# AQPCB.net
KiCad netlist of a schematic drawn in EAGLE
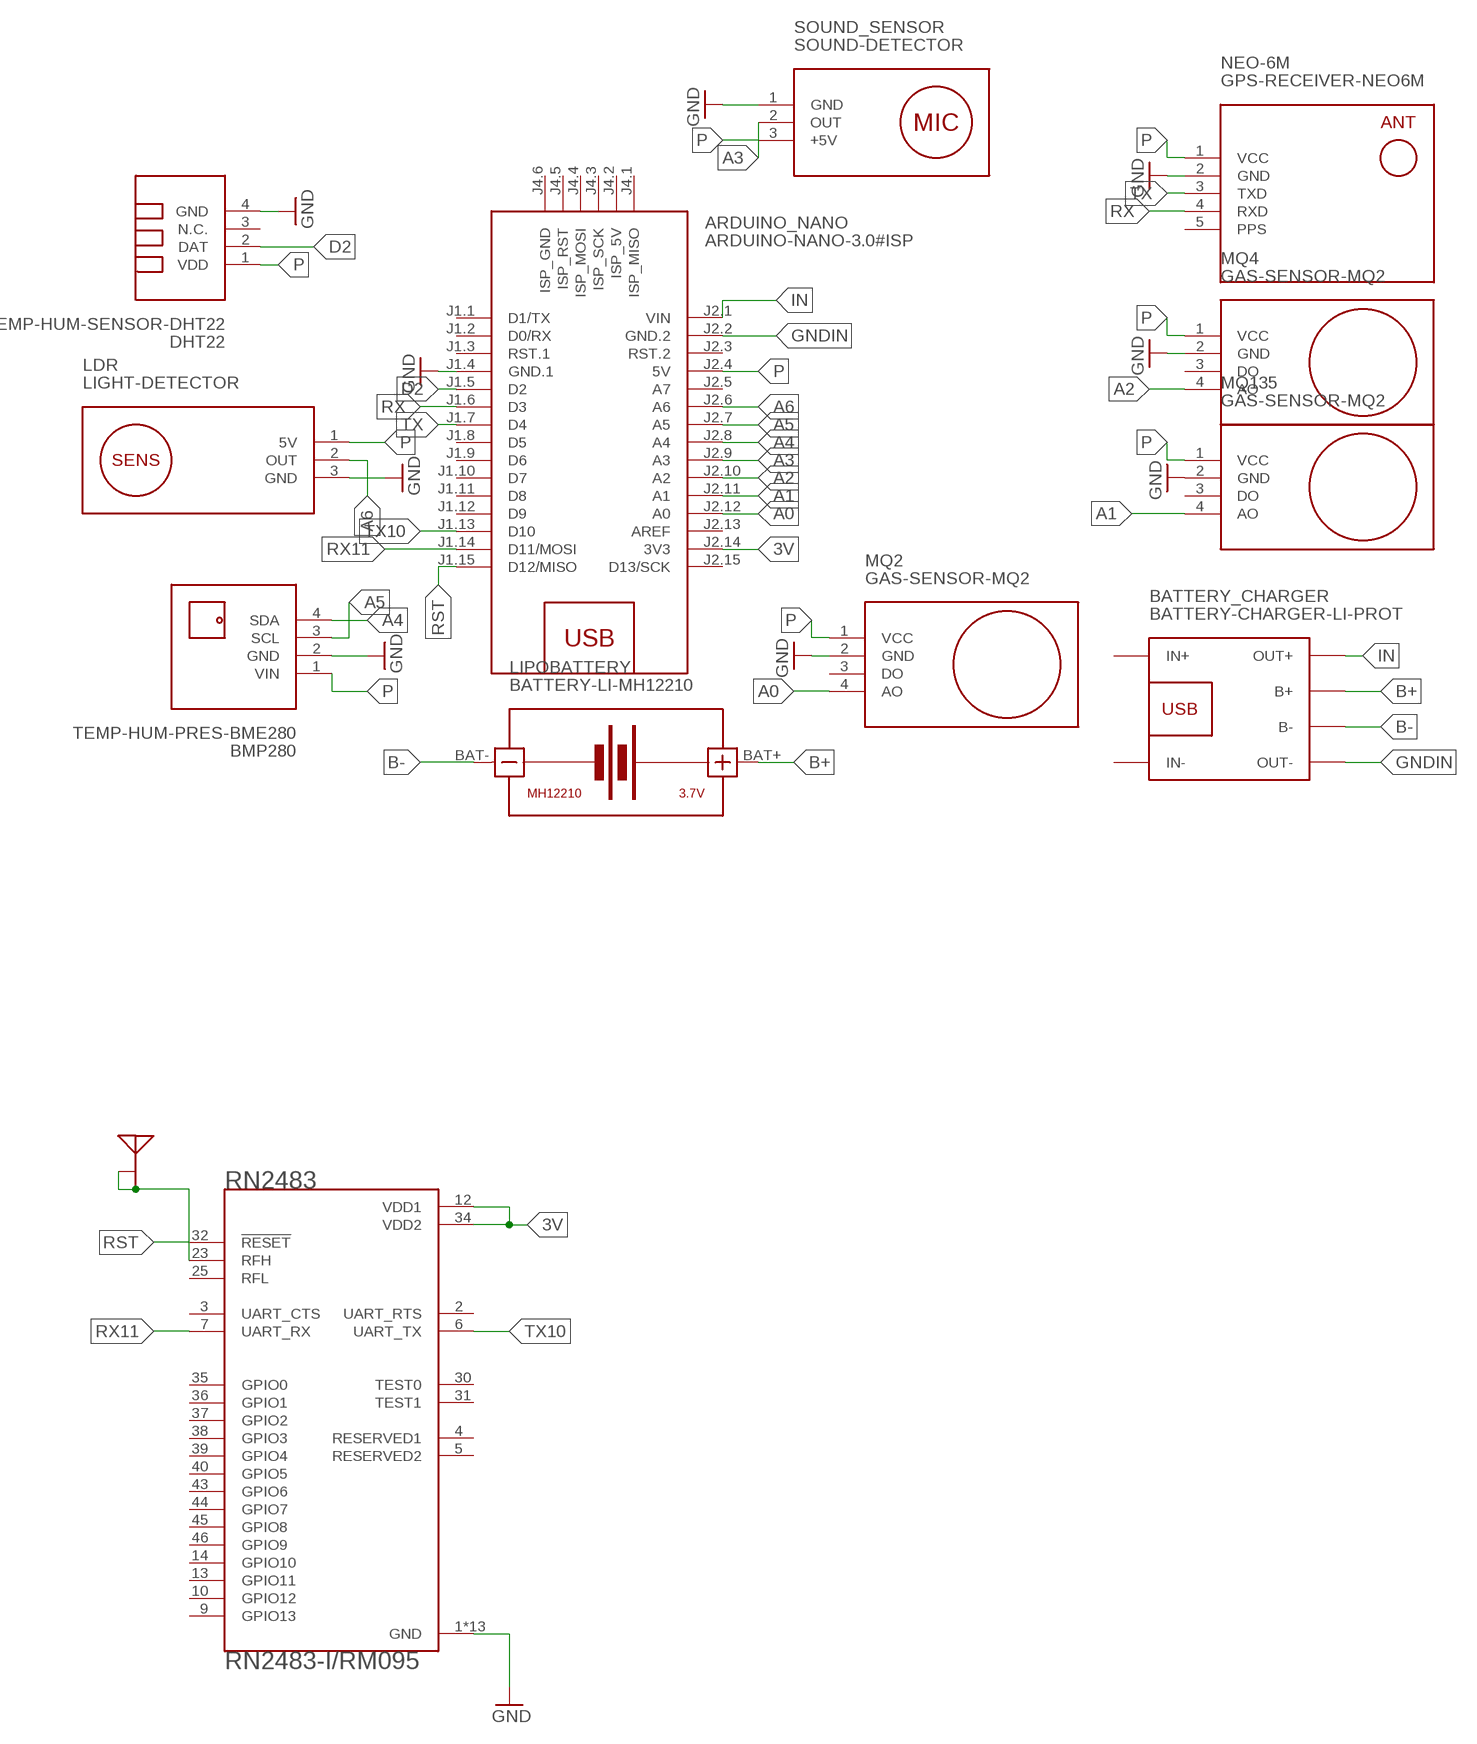
[diagram p0: schematic, sheet 1]

(export (version "E")
  (design (tool "Eeschema 10.0.6"))
  (components
    (comp (ref "ANTENNA")
      (value "CHIP")
      (footprint "eagle-import:2450AT18B100")
      (libsource (lib "eagle-import") (part "CHIP"))
    )
    (comp (ref "ARDUINO_NANO")
      (value "ARDUINO-NANO-3.0#ISP")
      (footprint "eagle-import:ARDUINO-NANO-3.0#ISP")
      (libsource (lib "eagle-import") (part "ARDUINO-NANO-3.0#ISP"))
    )
    (comp (ref "BATTERY_CHARGER")
      (value "BATTERY-CHARGER-LI-PROT")
      (footprint "eagle-import:BATTERY-CHARGER-LI-PROT")
      (libsource (lib "eagle-import") (part "BATTERY-CHARGER-LI-PROT"))
    )
    (comp (ref "BMP280")
      (value "TEMP-HUM-PRES-BME280")
      (footprint "eagle-import:TEMP-HUM-PRES-BME280")
      (libsource (lib "eagle-import") (part "TEMP-HUM-PRES-BME280"))
    )
    (comp (ref "DHT22")
      (value "TEMP-HUM-SENSOR-DHT22")
      (footprint "eagle-import:TEMP-HUM-SENSOR-DHT22")
      (libsource (lib "eagle-import") (part "TEMP-HUM-SENSOR-DHT22"))
    )
    (comp (ref "LDR")
      (value "LIGHT-DETECTOR")
      (footprint "eagle-import:LIGHT-DETECTOR")
      (libsource (lib "eagle-import") (part "LIGHT-DETECTOR"))
    )
    (comp (ref "LIPOBATTERY")
      (value "BATTERY-LI-MH12210")
      (footprint "eagle-import:BATTERY-LI-MH12210")
      (libsource (lib "eagle-import") (part "BATTERY-LI-MH12210"))
    )
    (comp (ref "MQ2")
      (value "GAS-SENSOR-MQ2")
      (footprint "eagle-import:GAS-SENSOR-MQ2")
      (libsource (lib "eagle-import") (part "GAS-SENSOR-MQ2"))
    )
    (comp (ref "MQ4")
      (value "GAS-SENSOR-MQ2")
      (footprint "eagle-import:GAS-SENSOR-MQ2")
      (libsource (lib "eagle-import") (part "GAS-SENSOR-MQ2"))
    )
    (comp (ref "MQ135")
      (value "GAS-SENSOR-MQ2")
      (footprint "eagle-import:GAS-SENSOR-MQ2")
      (libsource (lib "eagle-import") (part "GAS-SENSOR-MQ2"))
    )
    (comp (ref "NEO-6M")
      (value "GPS-RECEIVER-NEO6M")
      (footprint "eagle-import:GPS-RECEIVER-NEO6M")
      (libsource (lib "eagle-import") (part "GPS-RECEIVER-NEO6M"))
    )
    (comp (ref "RN2483")
      (value "RN2483-I/RM095")
      (footprint "eagle-import:MICROCHIP_RN2483-I_RM095")
      (fields (field (name "MF") "Microchip"))
      (libsource (lib "eagle-import") (part "RN2483-I/RM095"))
    )
    (comp (ref "SOUND_SENSOR")
      (value "SOUND-DETECTOR")
      (footprint "eagle-import:SOUND-DETECTOR")
      (libsource (lib "eagle-import") (part "SOUND-DETECTOR"))
    )
  )
  (nets
    (net (code "1") (name "/PPS") (class "Default")
      (node (ref "NEO-6M") (pin "5") (pinfunction "PPS_5") (pintype "power_in"))
    )
    (net (code "2") (name "3V") (class "Default")
      (node (ref "ARDUINO_NANO") (pin "J2.14") (pinfunction "3V3_J2.14") (pintype "power_in"))
      (node (ref "RN2483") (pin "12") (pinfunction "VDD1_12") (pintype "power_in"))
      (node (ref "RN2483") (pin "34") (pinfunction "VDD2_34") (pintype "power_in"))
    )
    (net (code "3") (name "A0") (class "Default")
      (node (ref "ARDUINO_NANO") (pin "J2.12") (pinfunction "A0_J2.12") (pintype "bidirectional"))
      (node (ref "MQ2") (pin "4") (pinfunction "AO_4") (pintype "output"))
    )
    (net (code "4") (name "A1") (class "Default")
      (node (ref "ARDUINO_NANO") (pin "J2.11") (pinfunction "A1_J2.11") (pintype "bidirectional"))
      (node (ref "MQ135") (pin "4") (pinfunction "AO_4") (pintype "output"))
    )
    (net (code "5") (name "A2") (class "Default")
      (node (ref "ARDUINO_NANO") (pin "J2.10") (pinfunction "A2_J2.10") (pintype "bidirectional"))
      (node (ref "MQ4") (pin "4") (pinfunction "AO_4") (pintype "output"))
    )
    (net (code "6") (name "A3") (class "Default")
      (node (ref "ARDUINO_NANO") (pin "J2.9") (pinfunction "A3_J2.9") (pintype "bidirectional"))
      (node (ref "SOUND_SENSOR") (pin "2") (pinfunction "OUT_2") (pintype "output"))
    )
    (net (code "7") (name "A4") (class "Default")
      (node (ref "ARDUINO_NANO") (pin "J2.8") (pinfunction "A4_J2.8") (pintype "bidirectional"))
      (node (ref "BMP280") (pin "4") (pinfunction "SDA_4") (pintype "bidirectional"))
    )
    (net (code "8") (name "A5") (class "Default")
      (node (ref "ARDUINO_NANO") (pin "J2.7") (pinfunction "A5_J2.7") (pintype "bidirectional"))
      (node (ref "BMP280") (pin "3") (pinfunction "SCL_3") (pintype "bidirectional"))
    )
    (net (code "9") (name "A6") (class "Default")
      (node (ref "ARDUINO_NANO") (pin "J2.6") (pinfunction "A6_J2.6") (pintype "bidirectional"))
      (node (ref "LDR") (pin "2") (pinfunction "OUT_2") (pintype "bidirectional"))
    )
    (net (code "10") (name "B+") (class "Default")
      (node (ref "BATTERY_CHARGER") (pin "B+") (pinfunction "B+_B+") (pintype "bidirectional"))
      (node (ref "LIPOBATTERY") (pin "BAT+") (pinfunction "BAT+_BAT+") (pintype "power_in"))
    )
    (net (code "11") (name "B-") (class "Default")
      (node (ref "BATTERY_CHARGER") (pin "B-") (pinfunction "B-_B-") (pintype "bidirectional"))
      (node (ref "LIPOBATTERY") (pin "BAT-") (pinfunction "BAT-_BAT-") (pintype "power_in"))
    )
    (net (code "12") (name "D2") (class "Default")
      (node (ref "ARDUINO_NANO") (pin "J1.5") (pinfunction "D2_J1.5") (pintype "bidirectional"))
      (node (ref "DHT22") (pin "2") (pinfunction "DAT_2") (pintype "bidirectional"))
    )
    (net (code "13") (name "GND") (class "Default")
      (node (ref "ARDUINO_NANO") (pin "J1.4") (pinfunction "GND.1_J1.4") (pintype "power_in"))
      (node (ref "BMP280") (pin "2") (pinfunction "GND_2") (pintype "power_in"))
      (node (ref "DHT22") (pin "4") (pinfunction "GND_4") (pintype "power_in"))
      (node (ref "LDR") (pin "3") (pinfunction "GND_3") (pintype "power_in"))
      (node (ref "MQ135") (pin "2") (pinfunction "GND_2") (pintype "power_in"))
      (node (ref "MQ2") (pin "2") (pinfunction "GND_2") (pintype "power_in"))
      (node (ref "MQ4") (pin "2") (pinfunction "GND_2") (pintype "power_in"))
      (node (ref "NEO-6M") (pin "2") (pinfunction "GND_2") (pintype "bidirectional"))
      (node (ref "RN2483") (pin "1") (pinfunction "GND_1") (pintype "passive"))
      (node (ref "RN2483") (pin "11") (pinfunction "GND_11") (pintype "passive"))
      (node (ref "RN2483") (pin "20") (pinfunction "GND_20") (pintype "passive"))
      (node (ref "RN2483") (pin "21") (pinfunction "GND_21") (pintype "passive"))
      (node (ref "RN2483") (pin "22") (pinfunction "GND_22") (pintype "passive"))
      (node (ref "RN2483") (pin "24") (pinfunction "GND_24") (pintype "passive"))
      (node (ref "RN2483") (pin "26") (pinfunction "GND_26") (pintype "passive"))
      (node (ref "RN2483") (pin "27") (pinfunction "GND_27") (pintype "passive"))
      (node (ref "RN2483") (pin "28") (pinfunction "GND_28") (pintype "passive"))
      (node (ref "RN2483") (pin "33") (pinfunction "GND_33") (pintype "passive"))
      (node (ref "RN2483") (pin "41") (pinfunction "GND_41") (pintype "passive"))
      (node (ref "RN2483") (pin "47") (pinfunction "GND_47") (pintype "passive"))
      (node (ref "RN2483") (pin "8") (pinfunction "GND_8") (pintype "passive"))
      (node (ref "SOUND_SENSOR") (pin "1") (pinfunction "GND_1") (pintype "power_in"))
    )
    (net (code "14") (name "GNDIN") (class "Default")
      (node (ref "ARDUINO_NANO") (pin "J2.2") (pinfunction "GND.2_J2.2") (pintype "power_in"))
      (node (ref "BATTERY_CHARGER") (pin "OUT-") (pinfunction "OUT-_OUT-") (pintype "bidirectional"))
    )
    (net (code "15") (name "IN") (class "Default")
      (node (ref "ARDUINO_NANO") (pin "J2.1") (pinfunction "VIN_J2.1") (pintype "power_in"))
      (node (ref "BATTERY_CHARGER") (pin "OUT+") (pinfunction "OUT+_OUT+") (pintype "bidirectional"))
    )
    (net (code "16") (name "Net-(RN2483-RFH)") (class "Default")
      (node (ref "ANTENNA") (pin "FEED") (pinfunction "FEED_FEED") (pintype "bidirectional"))
      (node (ref "ANTENNA") (pin "GND") (pinfunction "GND_GND") (pintype "bidirectional"))
      (node (ref "RN2483") (pin "23") (pinfunction "RFH_23") (pintype "input"))
    )
    (net (code "17") (name "P") (class "Default")
      (node (ref "ARDUINO_NANO") (pin "J2.4") (pinfunction "5V_J2.4") (pintype "power_in"))
      (node (ref "BMP280") (pin "1") (pinfunction "VIN_1") (pintype "power_in"))
      (node (ref "DHT22") (pin "1") (pinfunction "VDD_1") (pintype "power_in"))
      (node (ref "LDR") (pin "1") (pinfunction "5V_1") (pintype "power_in"))
      (node (ref "MQ135") (pin "1") (pinfunction "VCC_1") (pintype "power_in"))
      (node (ref "MQ2") (pin "1") (pinfunction "VCC_1") (pintype "power_in"))
      (node (ref "MQ4") (pin "1") (pinfunction "VCC_1") (pintype "power_in"))
      (node (ref "NEO-6M") (pin "1") (pinfunction "VCC_1") (pintype "bidirectional"))
      (node (ref "SOUND_SENSOR") (pin "3") (pinfunction "+5V_3") (pintype "power_in"))
    )
    (net (code "18") (name "RST") (class "Default")
      (node (ref "ARDUINO_NANO") (pin "J1.15") (pinfunction "D12/MISO_J1.15") (pintype "bidirectional"))
      (node (ref "RN2483") (pin "32") (pinfunction "~{RESET}_32") (pintype "input"))
    )
    (net (code "19") (name "RX") (class "Default")
      (node (ref "ARDUINO_NANO") (pin "J1.6") (pinfunction "D3_J1.6") (pintype "bidirectional"))
      (node (ref "NEO-6M") (pin "4") (pinfunction "RXD_4") (pintype "power_in"))
    )
    (net (code "20") (name "RX11") (class "Default")
      (node (ref "ARDUINO_NANO") (pin "J1.14") (pinfunction "D11/MOSI_J1.14") (pintype "bidirectional"))
      (node (ref "RN2483") (pin "7") (pinfunction "UART_RX_7") (pintype "input"))
    )
    (net (code "21") (name "TX") (class "Default")
      (node (ref "ARDUINO_NANO") (pin "J1.7") (pinfunction "D4_J1.7") (pintype "bidirectional"))
      (node (ref "NEO-6M") (pin "3") (pinfunction "TXD_3") (pintype "bidirectional"))
    )
    (net (code "22") (name "TX10") (class "Default")
      (node (ref "ARDUINO_NANO") (pin "J1.13") (pinfunction "D10_J1.13") (pintype "bidirectional"))
      (node (ref "RN2483") (pin "6") (pinfunction "UART_TX_6") (pintype "output"))
    )
    (net (code "23") (name "unconnected-(ARDUINO_NANO-A7-PadJ2.5)") (class "Default")
      (node (ref "ARDUINO_NANO") (pin "J2.5") (pinfunction "A7_J2.5") (pintype "bidirectional"))
    )
    (net (code "24") (name "unconnected-(ARDUINO_NANO-AREF-PadJ2.13)") (class "Default")
      (node (ref "ARDUINO_NANO") (pin "J2.13") (pinfunction "AREF_J2.13") (pintype "bidirectional"))
    )
    (net (code "25") (name "unconnected-(ARDUINO_NANO-D0{slash}RX-PadJ1.2)") (class "Default")
      (node (ref "ARDUINO_NANO") (pin "J1.2") (pinfunction "D0/RX_J1.2") (pintype "bidirectional"))
    )
    (net (code "26") (name "unconnected-(ARDUINO_NANO-D1{slash}TX-PadJ1.1)") (class "Default")
      (node (ref "ARDUINO_NANO") (pin "J1.1") (pinfunction "D1/TX_J1.1") (pintype "bidirectional"))
    )
    (net (code "27") (name "unconnected-(ARDUINO_NANO-D5-PadJ1.8)") (class "Default")
      (node (ref "ARDUINO_NANO") (pin "J1.8") (pinfunction "D5_J1.8") (pintype "bidirectional"))
    )
    (net (code "28") (name "unconnected-(ARDUINO_NANO-D6-PadJ1.9)") (class "Default")
      (node (ref "ARDUINO_NANO") (pin "J1.9") (pinfunction "D6_J1.9") (pintype "bidirectional"))
    )
    (net (code "29") (name "unconnected-(ARDUINO_NANO-D7-PadJ1.10)") (class "Default")
      (node (ref "ARDUINO_NANO") (pin "J1.10") (pinfunction "D7_J1.10") (pintype "bidirectional"))
    )
    (net (code "30") (name "unconnected-(ARDUINO_NANO-D8-PadJ1.11)") (class "Default")
      (node (ref "ARDUINO_NANO") (pin "J1.11") (pinfunction "D8_J1.11") (pintype "bidirectional"))
    )
    (net (code "31") (name "unconnected-(ARDUINO_NANO-D9-PadJ1.12)") (class "Default")
      (node (ref "ARDUINO_NANO") (pin "J1.12") (pinfunction "D9_J1.12") (pintype "bidirectional"))
    )
    (net (code "32") (name "unconnected-(ARDUINO_NANO-D13{slash}SCK-PadJ2.15)") (class "Default")
      (node (ref "ARDUINO_NANO") (pin "J2.15") (pinfunction "D13/SCK_J2.15") (pintype "bidirectional"))
    )
    (net (code "33") (name "unconnected-(ARDUINO_NANO-ISP_5V-PadJ4.2)") (class "Default")
      (node (ref "ARDUINO_NANO") (pin "J4.2") (pinfunction "ISP_5V_J4.2") (pintype "bidirectional"))
    )
    (net (code "34") (name "unconnected-(ARDUINO_NANO-ISP_GND-PadJ4.6)") (class "Default")
      (node (ref "ARDUINO_NANO") (pin "J4.6") (pinfunction "ISP_GND_J4.6") (pintype "bidirectional"))
    )
    (net (code "35") (name "unconnected-(ARDUINO_NANO-ISP_MISO-PadJ4.1)") (class "Default")
      (node (ref "ARDUINO_NANO") (pin "J4.1") (pinfunction "ISP_MISO_J4.1") (pintype "bidirectional"))
    )
    (net (code "36") (name "unconnected-(ARDUINO_NANO-ISP_MOSI-PadJ4.4)") (class "Default")
      (node (ref "ARDUINO_NANO") (pin "J4.4") (pinfunction "ISP_MOSI_J4.4") (pintype "bidirectional"))
    )
    (net (code "37") (name "unconnected-(ARDUINO_NANO-ISP_RST-PadJ4.5)") (class "Default")
      (node (ref "ARDUINO_NANO") (pin "J4.5") (pinfunction "ISP_RST_J4.5") (pintype "bidirectional"))
    )
    (net (code "38") (name "unconnected-(ARDUINO_NANO-ISP_SCK-PadJ4.3)") (class "Default")
      (node (ref "ARDUINO_NANO") (pin "J4.3") (pinfunction "ISP_SCK_J4.3") (pintype "bidirectional"))
    )
    (net (code "39") (name "unconnected-(ARDUINO_NANO-RST.1-PadJ1.3)") (class "Default")
      (node (ref "ARDUINO_NANO") (pin "J1.3") (pinfunction "RST.1_J1.3") (pintype "bidirectional"))
    )
    (net (code "40") (name "unconnected-(ARDUINO_NANO-RST.2-PadJ2.3)") (class "Default")
      (node (ref "ARDUINO_NANO") (pin "J2.3") (pinfunction "RST.2_J2.3") (pintype "bidirectional"))
    )
    (net (code "41") (name "unconnected-(BATTERY_CHARGER-PadIN+)") (class "Default")
      (node (ref "BATTERY_CHARGER") (pin "IN+") (pinfunction "IN+_IN+") (pintype "bidirectional"))
    )
    (net (code "42") (name "unconnected-(BATTERY_CHARGER-PadIN-)") (class "Default")
      (node (ref "BATTERY_CHARGER") (pin "IN-") (pinfunction "IN-_IN-") (pintype "bidirectional"))
    )
    (net (code "43") (name "unconnected-(DHT22-N.C.-Pad3)") (class "Default")
      (node (ref "DHT22") (pin "3") (pinfunction "N.C._3") (pintype "passive"))
    )
    (net (code "44") (name "unconnected-(MQ2-DO-Pad3)") (class "Default")
      (node (ref "MQ2") (pin "3") (pinfunction "DO_3") (pintype "output"))
    )
    (net (code "45") (name "unconnected-(MQ4-DO-Pad3)") (class "Default")
      (node (ref "MQ4") (pin "3") (pinfunction "DO_3") (pintype "output"))
    )
    (net (code "46") (name "unconnected-(MQ135-DO-Pad3)") (class "Default")
      (node (ref "MQ135") (pin "3") (pinfunction "DO_3") (pintype "output"))
    )
    (net (code "47") (name "unconnected-(RN2483-GPIO0-Pad35)") (class "Default")
      (node (ref "RN2483") (pin "35") (pinfunction "GPIO0_35") (pintype "bidirectional"))
    )
    (net (code "48") (name "unconnected-(RN2483-GPIO1-Pad36)") (class "Default")
      (node (ref "RN2483") (pin "36") (pinfunction "GPIO1_36") (pintype "bidirectional"))
    )
    (net (code "49") (name "unconnected-(RN2483-GPIO2-Pad37)") (class "Default")
      (node (ref "RN2483") (pin "37") (pinfunction "GPIO2_37") (pintype "bidirectional"))
    )
    (net (code "50") (name "unconnected-(RN2483-GPIO3-Pad38)") (class "Default")
      (node (ref "RN2483") (pin "38") (pinfunction "GPIO3_38") (pintype "bidirectional"))
    )
    (net (code "51") (name "unconnected-(RN2483-GPIO4-Pad39)") (class "Default")
      (node (ref "RN2483") (pin "39") (pinfunction "GPIO4_39") (pintype "bidirectional"))
    )
    (net (code "52") (name "unconnected-(RN2483-GPIO5-Pad40)") (class "Default")
      (node (ref "RN2483") (pin "40") (pinfunction "GPIO5_40") (pintype "bidirectional"))
    )
    (net (code "53") (name "unconnected-(RN2483-GPIO6-Pad43)") (class "Default")
      (node (ref "RN2483") (pin "43") (pinfunction "GPIO6_43") (pintype "bidirectional"))
    )
    (net (code "54") (name "unconnected-(RN2483-GPIO7-Pad44)") (class "Default")
      (node (ref "RN2483") (pin "44") (pinfunction "GPIO7_44") (pintype "bidirectional"))
    )
    (net (code "55") (name "unconnected-(RN2483-GPIO8-Pad45)") (class "Default")
      (node (ref "RN2483") (pin "45") (pinfunction "GPIO8_45") (pintype "bidirectional"))
    )
    (net (code "56") (name "unconnected-(RN2483-GPIO9-Pad46)") (class "Default")
      (node (ref "RN2483") (pin "46") (pinfunction "GPIO9_46") (pintype "bidirectional"))
    )
    (net (code "57") (name "unconnected-(RN2483-GPIO10-Pad14)") (class "Default")
      (node (ref "RN2483") (pin "14") (pinfunction "GPIO10_14") (pintype "bidirectional"))
    )
    (net (code "58") (name "unconnected-(RN2483-GPIO11-Pad13)") (class "Default")
      (node (ref "RN2483") (pin "13") (pinfunction "GPIO11_13") (pintype "bidirectional"))
    )
    (net (code "59") (name "unconnected-(RN2483-GPIO12-Pad10)") (class "Default")
      (node (ref "RN2483") (pin "10") (pinfunction "GPIO12_10") (pintype "bidirectional"))
    )
    (net (code "60") (name "unconnected-(RN2483-GPIO13-Pad9)") (class "Default")
      (node (ref "RN2483") (pin "9") (pinfunction "GPIO13_9") (pintype "bidirectional"))
    )
    (net (code "61") (name "unconnected-(RN2483-RESERVED1-Pad4)") (class "Default")
      (node (ref "RN2483") (pin "4") (pinfunction "RESERVED1_4") (pintype "passive"))
    )
    (net (code "62") (name "unconnected-(RN2483-RESERVED2-Pad5)") (class "Default")
      (node (ref "RN2483") (pin "5") (pinfunction "RESERVED2_5") (pintype "passive"))
    )
    (net (code "63") (name "unconnected-(RN2483-RFL-Pad25)") (class "Default")
      (node (ref "RN2483") (pin "25") (pinfunction "RFL_25") (pintype "input"))
    )
    (net (code "64") (name "unconnected-(RN2483-TEST0-Pad30)") (class "Default")
      (node (ref "RN2483") (pin "30") (pinfunction "TEST0_30") (pintype "passive"))
    )
    (net (code "65") (name "unconnected-(RN2483-TEST1-Pad31)") (class "Default")
      (node (ref "RN2483") (pin "31") (pinfunction "TEST1_31") (pintype "passive"))
    )
    (net (code "66") (name "unconnected-(RN2483-UART_CTS-Pad3)") (class "Default")
      (node (ref "RN2483") (pin "3") (pinfunction "UART_CTS_3") (pintype "input"))
    )
    (net (code "67") (name "unconnected-(RN2483-UART_RTS-Pad2)") (class "Default")
      (node (ref "RN2483") (pin "2") (pinfunction "UART_RTS_2") (pintype "output"))
    )
  )
)
